# LED-DRIVER.net
KiCad netlist of a schematic drawn in Altium Designer
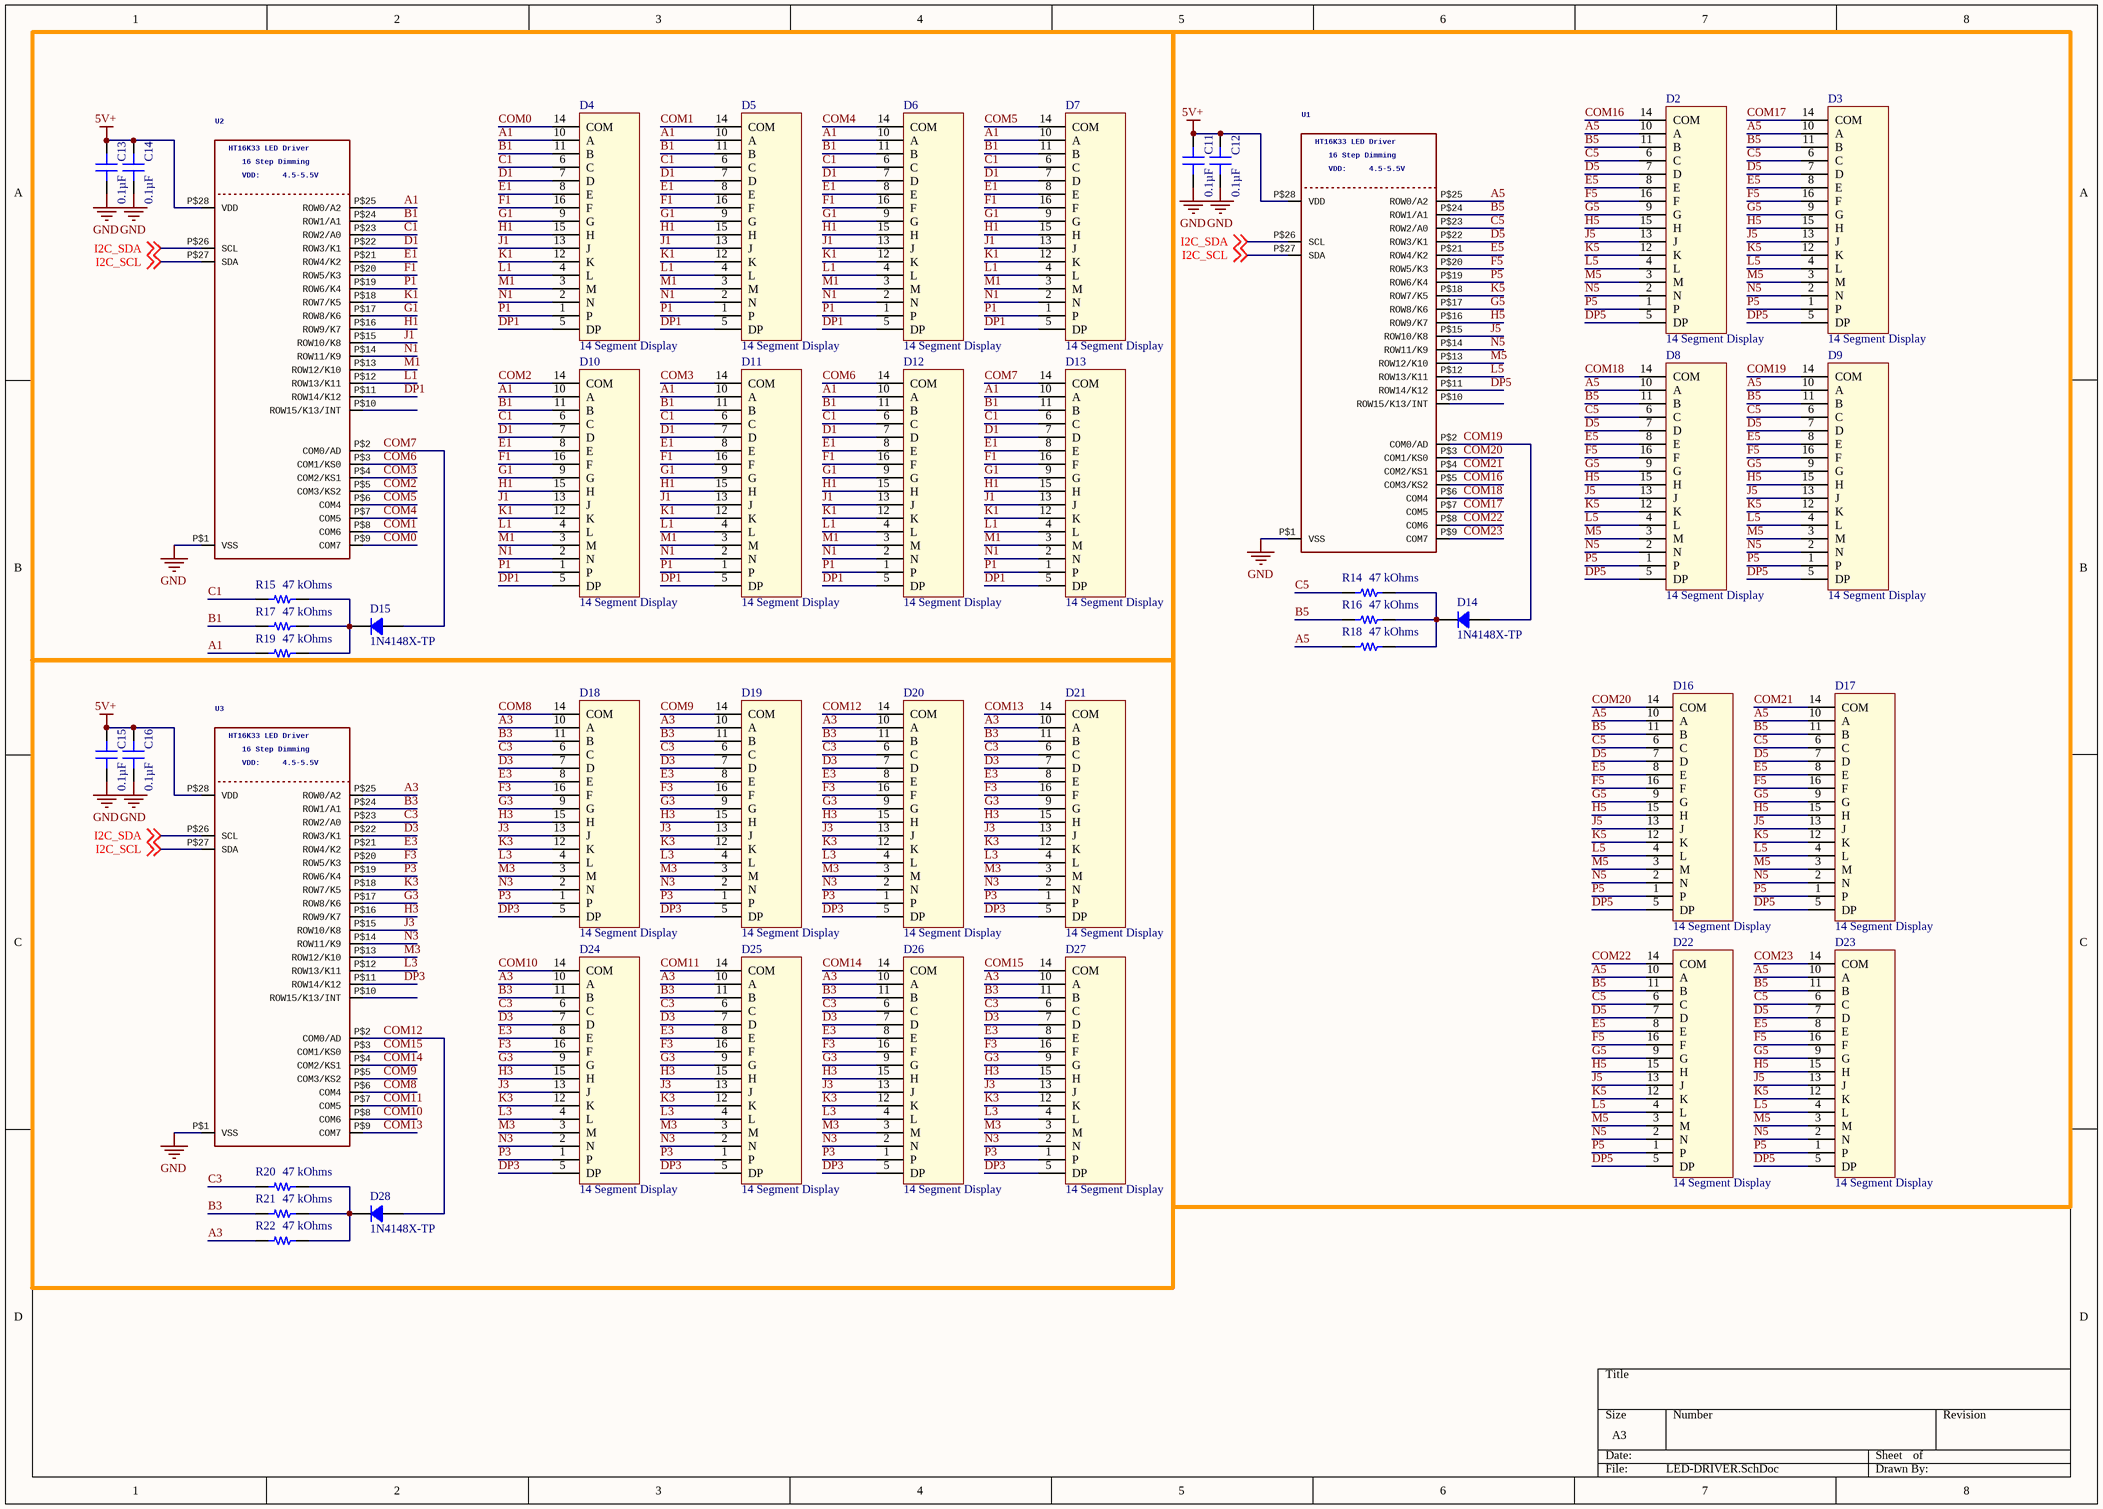
[diagram p0: LED-DRIVER.SchDoc]

(export (version "E")
  (design (tool "Eeschema 10.0.6"))
  (components
    (comp (ref "C11")
      (value "0.1µF")
      (footprint "CAP 0603_1608")
      (description "CAP CER 0.1UF 25V X7R 0603")
      (fields (field (name "PART NUMBER") "C0603T104K3RAL7867") (field (name "MANUFACTURER") "KEMET"))
      (libsource (lib "Altium Master") (part "Capacitor"))
    )
    (comp (ref "C12")
      (value "0.1µF")
      (footprint "CAP 0603_1608")
      (description "CAP CER 0.1UF 25V X7R 0603")
      (fields (field (name "PART NUMBER") "C0603T104K3RAL7867") (field (name "MANUFACTURER") "KEMET"))
      (libsource (lib "Altium Master") (part "Capacitor"))
    )
    (comp (ref "C13")
      (value "0.1µF")
      (footprint "CAP 0603_1608")
      (description "CAP CER 0.1UF 25V X7R 0603")
      (fields (field (name "PART NUMBER") "C0603T104K3RAL7867") (field (name "MANUFACTURER") "KEMET"))
      (libsource (lib "Altium Master") (part "Capacitor"))
    )
    (comp (ref "C14")
      (value "0.1µF")
      (footprint "CAP 0603_1608")
      (description "CAP CER 0.1UF 25V X7R 0603")
      (fields (field (name "PART NUMBER") "C0603T104K3RAL7867") (field (name "MANUFACTURER") "KEMET"))
      (libsource (lib "Altium Master") (part "Capacitor"))
    )
    (comp (ref "C15")
      (value "0.1µF")
      (footprint "CAP 0603_1608")
      (description "CAP CER 0.1UF 25V X7R 0603")
      (fields (field (name "PART NUMBER") "C0603T104K3RAL7867") (field (name "MANUFACTURER") "KEMET"))
      (libsource (lib "Altium Master") (part "Capacitor"))
    )
    (comp (ref "C16")
      (value "0.1µF")
      (footprint "CAP 0603_1608")
      (description "CAP CER 0.1UF 25V X7R 0603")
      (fields (field (name "PART NUMBER") "C0603T104K3RAL7867") (field (name "MANUFACTURER") "KEMET"))
      (libsource (lib "Altium Master") (part "Capacitor"))
    )
    (comp (ref "D2")
      (value "14 Segment Display")
      (footprint "14 Seg Display")
      (description "14 Segment display red 2 char")
      (libsource (lib "Lib") (part "14 Segment Display"))
    )
    (comp (ref "D3")
      (value "14 Segment Display")
      (footprint "14 Seg Display")
      (description "14 Segment display red 2 char")
      (libsource (lib "Lib") (part "14 Segment Display"))
    )
    (comp (ref "D4")
      (value "14 Segment Display")
      (footprint "14 Seg Display")
      (description "14 Segment display red 2 char")
      (libsource (lib "Lib") (part "14 Segment Display"))
    )
    (comp (ref "D5")
      (value "14 Segment Display")
      (footprint "14 Seg Display")
      (description "14 Segment display red 2 char")
      (libsource (lib "Lib") (part "14 Segment Display"))
    )
    (comp (ref "D6")
      (value "14 Segment Display")
      (footprint "14 Seg Display")
      (description "14 Segment display red 2 char")
      (libsource (lib "Lib") (part "14 Segment Display"))
    )
    (comp (ref "D7")
      (value "14 Segment Display")
      (footprint "14 Seg Display")
      (description "14 Segment display red 2 char")
      (libsource (lib "Lib") (part "14 Segment Display"))
    )
    (comp (ref "D8")
      (value "14 Segment Display")
      (footprint "14 Seg Display")
      (description "14 Segment display red 2 char")
      (libsource (lib "Lib") (part "14 Segment Display"))
    )
    (comp (ref "D9")
      (value "14 Segment Display")
      (footprint "14 Seg Display")
      (description "14 Segment display red 2 char")
      (libsource (lib "Lib") (part "14 Segment Display"))
    )
    (comp (ref "D10")
      (value "14 Segment Display")
      (footprint "14 Seg Display")
      (description "14 Segment display red 2 char")
      (libsource (lib "Lib") (part "14 Segment Display"))
    )
    (comp (ref "D11")
      (value "14 Segment Display")
      (footprint "14 Seg Display")
      (description "14 Segment display red 2 char")
      (libsource (lib "Lib") (part "14 Segment Display"))
    )
    (comp (ref "D12")
      (value "14 Segment Display")
      (footprint "14 Seg Display")
      (description "14 Segment display red 2 char")
      (libsource (lib "Lib") (part "14 Segment Display"))
    )
    (comp (ref "D13")
      (value "14 Segment Display")
      (footprint "14 Seg Display")
      (description "14 Segment display red 2 char")
      (libsource (lib "Lib") (part "14 Segment Display"))
    )
    (comp (ref "D14")
      (value "1N4148X-TP")
      (footprint "SOD-523")
      (description "DIODE GEN PURP 75V 150MA SOD523")
      (fields (field (name "MANUFACTURER") "Micro Commercial Co"))
      (libsource (lib "Altium Master") (part "Diode"))
    )
    (comp (ref "D15")
      (value "1N4148X-TP")
      (footprint "SOD-523")
      (description "DIODE GEN PURP 75V 150MA SOD523")
      (fields (field (name "MANUFACTURER") "Micro Commercial Co"))
      (libsource (lib "Altium Master") (part "Diode"))
    )
    (comp (ref "D16")
      (value "14 Segment Display")
      (footprint "14 Seg Display")
      (description "14 Segment display red 2 char")
      (libsource (lib "Lib") (part "14 Segment Display"))
    )
    (comp (ref "D17")
      (value "14 Segment Display")
      (footprint "14 Seg Display")
      (description "14 Segment display red 2 char")
      (libsource (lib "Lib") (part "14 Segment Display"))
    )
    (comp (ref "D18")
      (value "14 Segment Display")
      (footprint "14 Seg Display")
      (description "14 Segment display red 2 char")
      (libsource (lib "Lib") (part "14 Segment Display"))
    )
    (comp (ref "D19")
      (value "14 Segment Display")
      (footprint "14 Seg Display")
      (description "14 Segment display red 2 char")
      (libsource (lib "Lib") (part "14 Segment Display"))
    )
    (comp (ref "D20")
      (value "14 Segment Display")
      (footprint "14 Seg Display")
      (description "14 Segment display red 2 char")
      (libsource (lib "Lib") (part "14 Segment Display"))
    )
    (comp (ref "D21")
      (value "14 Segment Display")
      (footprint "14 Seg Display")
      (description "14 Segment display red 2 char")
      (libsource (lib "Lib") (part "14 Segment Display"))
    )
    (comp (ref "D22")
      (value "14 Segment Display")
      (footprint "14 Seg Display")
      (description "14 Segment display red 2 char")
      (libsource (lib "Lib") (part "14 Segment Display"))
    )
    (comp (ref "D23")
      (value "14 Segment Display")
      (footprint "14 Seg Display")
      (description "14 Segment display red 2 char")
      (libsource (lib "Lib") (part "14 Segment Display"))
    )
    (comp (ref "D24")
      (value "14 Segment Display")
      (footprint "14 Seg Display")
      (description "14 Segment display red 2 char")
      (libsource (lib "Lib") (part "14 Segment Display"))
    )
    (comp (ref "D25")
      (value "14 Segment Display")
      (footprint "14 Seg Display")
      (description "14 Segment display red 2 char")
      (libsource (lib "Lib") (part "14 Segment Display"))
    )
    (comp (ref "D26")
      (value "14 Segment Display")
      (footprint "14 Seg Display")
      (description "14 Segment display red 2 char")
      (libsource (lib "Lib") (part "14 Segment Display"))
    )
    (comp (ref "D27")
      (value "14 Segment Display")
      (footprint "14 Seg Display")
      (description "14 Segment display red 2 char")
      (libsource (lib "Lib") (part "14 Segment Display"))
    )
    (comp (ref "D28")
      (value "1N4148X-TP")
      (footprint "SOD-523")
      (description "DIODE GEN PURP 75V 150MA SOD523")
      (fields (field (name "MANUFACTURER") "Micro Commercial Co"))
      (libsource (lib "Altium Master") (part "Diode"))
    )
    (comp (ref "R14")
      (value "47 kOhms")
      (footprint "RES 0603_1608")
      (description "RES SMD 47K OHM 0.1% 1/10W 0603")
      (fields
        (field (name "PART NUMBER") "ERA-3AEB473V")
        (field (name "MANUFACTURER") "Panasonic Electronic Components")
      )
      (libsource (lib "Altium Master") (part "Resistor"))
    )
    (comp (ref "R15")
      (value "47 kOhms")
      (footprint "RES 0603_1608")
      (description "RES SMD 47K OHM 0.1% 1/10W 0603")
      (fields
        (field (name "PART NUMBER") "ERA-3AEB473V")
        (field (name "MANUFACTURER") "Panasonic Electronic Components")
      )
      (libsource (lib "Altium Master") (part "Resistor"))
    )
    (comp (ref "R16")
      (value "47 kOhms")
      (footprint "RES 0603_1608")
      (description "RES SMD 47K OHM 0.1% 1/10W 0603")
      (fields
        (field (name "PART NUMBER") "ERA-3AEB473V")
        (field (name "MANUFACTURER") "Panasonic Electronic Components")
      )
      (libsource (lib "Altium Master") (part "Resistor"))
    )
    (comp (ref "R17")
      (value "47 kOhms")
      (footprint "RES 0603_1608")
      (description "RES SMD 47K OHM 0.1% 1/10W 0603")
      (fields
        (field (name "PART NUMBER") "ERA-3AEB473V")
        (field (name "MANUFACTURER") "Panasonic Electronic Components")
      )
      (libsource (lib "Altium Master") (part "Resistor"))
    )
    (comp (ref "R18")
      (value "47 kOhms")
      (footprint "RES 0603_1608")
      (description "RES SMD 47K OHM 0.1% 1/10W 0603")
      (fields
        (field (name "PART NUMBER") "ERA-3AEB473V")
        (field (name "MANUFACTURER") "Panasonic Electronic Components")
      )
      (libsource (lib "Altium Master") (part "Resistor"))
    )
    (comp (ref "R19")
      (value "47 kOhms")
      (footprint "RES 0603_1608")
      (description "RES SMD 47K OHM 0.1% 1/10W 0603")
      (fields
        (field (name "PART NUMBER") "ERA-3AEB473V")
        (field (name "MANUFACTURER") "Panasonic Electronic Components")
      )
      (libsource (lib "Altium Master") (part "Resistor"))
    )
    (comp (ref "R20")
      (value "47 kOhms")
      (footprint "RES 0603_1608")
      (description "RES SMD 47K OHM 0.1% 1/10W 0603")
      (fields
        (field (name "PART NUMBER") "ERA-3AEB473V")
        (field (name "MANUFACTURER") "Panasonic Electronic Components")
      )
      (libsource (lib "Altium Master") (part "Resistor"))
    )
    (comp (ref "R21")
      (value "47 kOhms")
      (footprint "RES 0603_1608")
      (description "RES SMD 47K OHM 0.1% 1/10W 0603")
      (fields
        (field (name "PART NUMBER") "ERA-3AEB473V")
        (field (name "MANUFACTURER") "Panasonic Electronic Components")
      )
      (libsource (lib "Altium Master") (part "Resistor"))
    )
    (comp (ref "R22")
      (value "47 kOhms")
      (footprint "RES 0603_1608")
      (description "RES SMD 47K OHM 0.1% 1/10W 0603")
      (fields
        (field (name "PART NUMBER") "ERA-3AEB473V")
        (field (name "MANUFACTURER") "Panasonic Electronic Components")
      )
      (libsource (lib "Altium Master") (part "Resistor"))
    )
    (comp (ref "U1")
      (value "HT16K33_SOP28_SKINNY")
      (footprint "SOP28_300MIL_SKINNY")
      (fields
        (field (name "HT16K33LEDDRIVER") "HT16K33 LED Driver")
        (field (name "VDD") "VDD:")
        (field (name "4.5-5.5V") "4.5-5.5V")
        (field (name "16STEPDIMMING") "16 Step Dimming")
      )
      (libsource (lib "AlphaNumeric Featherwing rev A") (part "HT16K33_SOP28_SKINNY"))
    )
    (comp (ref "U2")
      (value "HT16K33_SOP28_SKINNY")
      (footprint "SOP28_300MIL_SKINNY")
      (fields
        (field (name "HT16K33LEDDRIVER") "HT16K33 LED Driver")
        (field (name "VDD") "VDD:")
        (field (name "4.5-5.5V") "4.5-5.5V")
        (field (name "16STEPDIMMING") "16 Step Dimming")
      )
      (libsource (lib "AlphaNumeric Featherwing rev A") (part "HT16K33_SOP28_SKINNY"))
    )
    (comp (ref "U3")
      (value "HT16K33_SOP28_SKINNY")
      (footprint "SOP28_300MIL_SKINNY")
      (fields
        (field (name "HT16K33LEDDRIVER") "HT16K33 LED Driver")
        (field (name "VDD") "VDD:")
        (field (name "4.5-5.5V") "4.5-5.5V")
        (field (name "16STEPDIMMING") "16 Step Dimming")
      )
      (libsource (lib "AlphaNumeric Featherwing rev A") (part "HT16K33_SOP28_SKINNY"))
    )
  )
  (nets
    (net (code "1") (name "/A1") (class "Default")
      (node (ref "D10") (pin "10") (pinfunction "A_10") (pintype "power_in"))
      (node (ref "D11") (pin "10") (pinfunction "A_10") (pintype "power_in"))
      (node (ref "D12") (pin "10") (pinfunction "A_10") (pintype "power_in"))
      (node (ref "D13") (pin "10") (pinfunction "A_10") (pintype "power_in"))
      (node (ref "D4") (pin "10") (pinfunction "A_10") (pintype "power_in"))
      (node (ref "D5") (pin "10") (pinfunction "A_10") (pintype "power_in"))
      (node (ref "D6") (pin "10") (pinfunction "A_10") (pintype "power_in"))
      (node (ref "D7") (pin "10") (pinfunction "A_10") (pintype "power_in"))
      (node (ref "R19") (pin "1") (pinfunction "1_1") (pintype "passive"))
      (node (ref "U2") (pin "P$25") (pinfunction "ROW0/A2_P$25") (pintype "bidirectional"))
    )
    (net (code "2") (name "/A3") (class "Default")
      (node (ref "D18") (pin "10") (pinfunction "A_10") (pintype "power_in"))
      (node (ref "D19") (pin "10") (pinfunction "A_10") (pintype "power_in"))
      (node (ref "D20") (pin "10") (pinfunction "A_10") (pintype "power_in"))
      (node (ref "D21") (pin "10") (pinfunction "A_10") (pintype "power_in"))
      (node (ref "D24") (pin "10") (pinfunction "A_10") (pintype "power_in"))
      (node (ref "D25") (pin "10") (pinfunction "A_10") (pintype "power_in"))
      (node (ref "D26") (pin "10") (pinfunction "A_10") (pintype "power_in"))
      (node (ref "D27") (pin "10") (pinfunction "A_10") (pintype "power_in"))
      (node (ref "R22") (pin "1") (pinfunction "1_1") (pintype "passive"))
      (node (ref "U3") (pin "P$25") (pinfunction "ROW0/A2_P$25") (pintype "bidirectional"))
    )
    (net (code "3") (name "/A5") (class "Default")
      (node (ref "D16") (pin "10") (pinfunction "A_10") (pintype "power_in"))
      (node (ref "D17") (pin "10") (pinfunction "A_10") (pintype "power_in"))
      (node (ref "D2") (pin "10") (pinfunction "A_10") (pintype "power_in"))
      (node (ref "D22") (pin "10") (pinfunction "A_10") (pintype "power_in"))
      (node (ref "D23") (pin "10") (pinfunction "A_10") (pintype "power_in"))
      (node (ref "D3") (pin "10") (pinfunction "A_10") (pintype "power_in"))
      (node (ref "D8") (pin "10") (pinfunction "A_10") (pintype "power_in"))
      (node (ref "D9") (pin "10") (pinfunction "A_10") (pintype "power_in"))
      (node (ref "R18") (pin "1") (pinfunction "1_1") (pintype "passive"))
      (node (ref "U1") (pin "P$25") (pinfunction "ROW0/A2_P$25") (pintype "bidirectional"))
    )
    (net (code "4") (name "/B1") (class "Default")
      (node (ref "D10") (pin "11") (pinfunction "B_11") (pintype "power_in"))
      (node (ref "D11") (pin "11") (pinfunction "B_11") (pintype "power_in"))
      (node (ref "D12") (pin "11") (pinfunction "B_11") (pintype "power_in"))
      (node (ref "D13") (pin "11") (pinfunction "B_11") (pintype "power_in"))
      (node (ref "D4") (pin "11") (pinfunction "B_11") (pintype "power_in"))
      (node (ref "D5") (pin "11") (pinfunction "B_11") (pintype "power_in"))
      (node (ref "D6") (pin "11") (pinfunction "B_11") (pintype "power_in"))
      (node (ref "D7") (pin "11") (pinfunction "B_11") (pintype "power_in"))
      (node (ref "R17") (pin "1") (pinfunction "1_1") (pintype "passive"))
      (node (ref "U2") (pin "P$24") (pinfunction "ROW1/A1_P$24") (pintype "bidirectional"))
    )
    (net (code "5") (name "/B3") (class "Default")
      (node (ref "D18") (pin "11") (pinfunction "B_11") (pintype "power_in"))
      (node (ref "D19") (pin "11") (pinfunction "B_11") (pintype "power_in"))
      (node (ref "D20") (pin "11") (pinfunction "B_11") (pintype "power_in"))
      (node (ref "D21") (pin "11") (pinfunction "B_11") (pintype "power_in"))
      (node (ref "D24") (pin "11") (pinfunction "B_11") (pintype "power_in"))
      (node (ref "D25") (pin "11") (pinfunction "B_11") (pintype "power_in"))
      (node (ref "D26") (pin "11") (pinfunction "B_11") (pintype "power_in"))
      (node (ref "D27") (pin "11") (pinfunction "B_11") (pintype "power_in"))
      (node (ref "R21") (pin "1") (pinfunction "1_1") (pintype "passive"))
      (node (ref "U3") (pin "P$24") (pinfunction "ROW1/A1_P$24") (pintype "bidirectional"))
    )
    (net (code "6") (name "/B5") (class "Default")
      (node (ref "D16") (pin "11") (pinfunction "B_11") (pintype "power_in"))
      (node (ref "D17") (pin "11") (pinfunction "B_11") (pintype "power_in"))
      (node (ref "D2") (pin "11") (pinfunction "B_11") (pintype "power_in"))
      (node (ref "D22") (pin "11") (pinfunction "B_11") (pintype "power_in"))
      (node (ref "D23") (pin "11") (pinfunction "B_11") (pintype "power_in"))
      (node (ref "D3") (pin "11") (pinfunction "B_11") (pintype "power_in"))
      (node (ref "D8") (pin "11") (pinfunction "B_11") (pintype "power_in"))
      (node (ref "D9") (pin "11") (pinfunction "B_11") (pintype "power_in"))
      (node (ref "R16") (pin "1") (pinfunction "1_1") (pintype "passive"))
      (node (ref "U1") (pin "P$24") (pinfunction "ROW1/A1_P$24") (pintype "bidirectional"))
    )
    (net (code "7") (name "/C1") (class "Default")
      (node (ref "D10") (pin "6") (pinfunction "C_6") (pintype "power_in"))
      (node (ref "D11") (pin "6") (pinfunction "C_6") (pintype "power_in"))
      (node (ref "D12") (pin "6") (pinfunction "C_6") (pintype "power_in"))
      (node (ref "D13") (pin "6") (pinfunction "C_6") (pintype "power_in"))
      (node (ref "D4") (pin "6") (pinfunction "C_6") (pintype "power_in"))
      (node (ref "D5") (pin "6") (pinfunction "C_6") (pintype "power_in"))
      (node (ref "D6") (pin "6") (pinfunction "C_6") (pintype "power_in"))
      (node (ref "D7") (pin "6") (pinfunction "C_6") (pintype "power_in"))
      (node (ref "R15") (pin "1") (pinfunction "1_1") (pintype "passive"))
      (node (ref "U2") (pin "P$23") (pinfunction "ROW2/A0_P$23") (pintype "bidirectional"))
    )
    (net (code "8") (name "/C3") (class "Default")
      (node (ref "D18") (pin "6") (pinfunction "C_6") (pintype "power_in"))
      (node (ref "D19") (pin "6") (pinfunction "C_6") (pintype "power_in"))
      (node (ref "D20") (pin "6") (pinfunction "C_6") (pintype "power_in"))
      (node (ref "D21") (pin "6") (pinfunction "C_6") (pintype "power_in"))
      (node (ref "D24") (pin "6") (pinfunction "C_6") (pintype "power_in"))
      (node (ref "D25") (pin "6") (pinfunction "C_6") (pintype "power_in"))
      (node (ref "D26") (pin "6") (pinfunction "C_6") (pintype "power_in"))
      (node (ref "D27") (pin "6") (pinfunction "C_6") (pintype "power_in"))
      (node (ref "R20") (pin "1") (pinfunction "1_1") (pintype "passive"))
      (node (ref "U3") (pin "P$23") (pinfunction "ROW2/A0_P$23") (pintype "bidirectional"))
    )
    (net (code "9") (name "/C5") (class "Default")
      (node (ref "D16") (pin "6") (pinfunction "C_6") (pintype "power_in"))
      (node (ref "D17") (pin "6") (pinfunction "C_6") (pintype "power_in"))
      (node (ref "D2") (pin "6") (pinfunction "C_6") (pintype "power_in"))
      (node (ref "D22") (pin "6") (pinfunction "C_6") (pintype "power_in"))
      (node (ref "D23") (pin "6") (pinfunction "C_6") (pintype "power_in"))
      (node (ref "D3") (pin "6") (pinfunction "C_6") (pintype "power_in"))
      (node (ref "D8") (pin "6") (pinfunction "C_6") (pintype "power_in"))
      (node (ref "D9") (pin "6") (pinfunction "C_6") (pintype "power_in"))
      (node (ref "R14") (pin "1") (pinfunction "1_1") (pintype "passive"))
      (node (ref "U1") (pin "P$23") (pinfunction "ROW2/A0_P$23") (pintype "bidirectional"))
    )
    (net (code "10") (name "/COM0") (class "Default")
      (node (ref "D4") (pin "14") (pinfunction "COM_14") (pintype "power_in"))
      (node (ref "U2") (pin "P$9") (pinfunction "COM7_P$9") (pintype "bidirectional"))
    )
    (net (code "11") (name "/COM1") (class "Default")
      (node (ref "D5") (pin "14") (pinfunction "COM_14") (pintype "power_in"))
      (node (ref "U2") (pin "P$8") (pinfunction "COM6_P$8") (pintype "bidirectional"))
    )
    (net (code "12") (name "/COM2") (class "Default")
      (node (ref "D10") (pin "14") (pinfunction "COM_14") (pintype "power_in"))
      (node (ref "U2") (pin "P$5") (pinfunction "COM3/KS2_P$5") (pintype "bidirectional"))
    )
    (net (code "13") (name "/COM3") (class "Default")
      (node (ref "D11") (pin "14") (pinfunction "COM_14") (pintype "power_in"))
      (node (ref "U2") (pin "P$4") (pinfunction "COM2/KS1_P$4") (pintype "bidirectional"))
    )
    (net (code "14") (name "/COM4") (class "Default")
      (node (ref "D6") (pin "14") (pinfunction "COM_14") (pintype "power_in"))
      (node (ref "U2") (pin "P$7") (pinfunction "COM5_P$7") (pintype "bidirectional"))
    )
    (net (code "15") (name "/COM5") (class "Default")
      (node (ref "D7") (pin "14") (pinfunction "COM_14") (pintype "power_in"))
      (node (ref "U2") (pin "P$6") (pinfunction "COM4_P$6") (pintype "bidirectional"))
    )
    (net (code "16") (name "/COM6") (class "Default")
      (node (ref "D12") (pin "14") (pinfunction "COM_14") (pintype "power_in"))
      (node (ref "U2") (pin "P$3") (pinfunction "COM1/KS0_P$3") (pintype "bidirectional"))
    )
    (net (code "17") (name "/COM7") (class "Default")
      (node (ref "D13") (pin "14") (pinfunction "COM_14") (pintype "power_in"))
      (node (ref "D15") (pin "1") (pinfunction "1_1") (pintype "passive"))
      (node (ref "U2") (pin "P$2") (pinfunction "COM0/AD_P$2") (pintype "bidirectional"))
    )
    (net (code "18") (name "/COM8") (class "Default")
      (node (ref "D18") (pin "14") (pinfunction "COM_14") (pintype "power_in"))
      (node (ref "U3") (pin "P$6") (pinfunction "COM4_P$6") (pintype "bidirectional"))
    )
    (net (code "19") (name "/COM9") (class "Default")
      (node (ref "D19") (pin "14") (pinfunction "COM_14") (pintype "power_in"))
      (node (ref "U3") (pin "P$5") (pinfunction "COM3/KS2_P$5") (pintype "bidirectional"))
    )
    (net (code "20") (name "/COM10") (class "Default")
      (node (ref "D24") (pin "14") (pinfunction "COM_14") (pintype "power_in"))
      (node (ref "U3") (pin "P$8") (pinfunction "COM6_P$8") (pintype "bidirectional"))
    )
    (net (code "21") (name "/COM11") (class "Default")
      (node (ref "D25") (pin "14") (pinfunction "COM_14") (pintype "power_in"))
      (node (ref "U3") (pin "P$7") (pinfunction "COM5_P$7") (pintype "bidirectional"))
    )
    (net (code "22") (name "/COM12") (class "Default")
      (node (ref "D20") (pin "14") (pinfunction "COM_14") (pintype "power_in"))
      (node (ref "D28") (pin "1") (pinfunction "1_1") (pintype "passive"))
      (node (ref "U3") (pin "P$2") (pinfunction "COM0/AD_P$2") (pintype "bidirectional"))
    )
    (net (code "23") (name "/COM13") (class "Default")
      (node (ref "D21") (pin "14") (pinfunction "COM_14") (pintype "power_in"))
      (node (ref "U3") (pin "P$9") (pinfunction "COM7_P$9") (pintype "bidirectional"))
    )
    (net (code "24") (name "/COM14") (class "Default")
      (node (ref "D26") (pin "14") (pinfunction "COM_14") (pintype "power_in"))
      (node (ref "U3") (pin "P$4") (pinfunction "COM2/KS1_P$4") (pintype "bidirectional"))
    )
    (net (code "25") (name "/COM15") (class "Default")
      (node (ref "D27") (pin "14") (pinfunction "COM_14") (pintype "power_in"))
      (node (ref "U3") (pin "P$3") (pinfunction "COM1/KS0_P$3") (pintype "bidirectional"))
    )
    (net (code "26") (name "/COM16") (class "Default")
      (node (ref "D2") (pin "14") (pinfunction "COM_14") (pintype "power_in"))
      (node (ref "U1") (pin "P$5") (pinfunction "COM3/KS2_P$5") (pintype "bidirectional"))
    )
    (net (code "27") (name "/COM17") (class "Default")
      (node (ref "D3") (pin "14") (pinfunction "COM_14") (pintype "power_in"))
      (node (ref "U1") (pin "P$7") (pinfunction "COM5_P$7") (pintype "bidirectional"))
    )
    (net (code "28") (name "/COM18") (class "Default")
      (node (ref "D8") (pin "14") (pinfunction "COM_14") (pintype "power_in"))
      (node (ref "U1") (pin "P$6") (pinfunction "COM4_P$6") (pintype "bidirectional"))
    )
    (net (code "29") (name "/COM19") (class "Default")
      (node (ref "D14") (pin "1") (pinfunction "1_1") (pintype "passive"))
      (node (ref "D9") (pin "14") (pinfunction "COM_14") (pintype "power_in"))
      (node (ref "U1") (pin "P$2") (pinfunction "COM0/AD_P$2") (pintype "bidirectional"))
    )
    (net (code "30") (name "/COM20") (class "Default")
      (node (ref "D16") (pin "14") (pinfunction "COM_14") (pintype "power_in"))
      (node (ref "U1") (pin "P$3") (pinfunction "COM1/KS0_P$3") (pintype "bidirectional"))
    )
    (net (code "31") (name "/COM21") (class "Default")
      (node (ref "D17") (pin "14") (pinfunction "COM_14") (pintype "power_in"))
      (node (ref "U1") (pin "P$4") (pinfunction "COM2/KS1_P$4") (pintype "bidirectional"))
    )
    (net (code "32") (name "/COM22") (class "Default")
      (node (ref "D22") (pin "14") (pinfunction "COM_14") (pintype "power_in"))
      (node (ref "U1") (pin "P$8") (pinfunction "COM6_P$8") (pintype "bidirectional"))
    )
    (net (code "33") (name "/COM23") (class "Default")
      (node (ref "D23") (pin "14") (pinfunction "COM_14") (pintype "power_in"))
      (node (ref "U1") (pin "P$9") (pinfunction "COM7_P$9") (pintype "bidirectional"))
    )
    (net (code "34") (name "/D1") (class "Default")
      (node (ref "D10") (pin "7") (pinfunction "D_7") (pintype "power_in"))
      (node (ref "D11") (pin "7") (pinfunction "D_7") (pintype "power_in"))
      (node (ref "D12") (pin "7") (pinfunction "D_7") (pintype "power_in"))
      (node (ref "D13") (pin "7") (pinfunction "D_7") (pintype "power_in"))
      (node (ref "D4") (pin "7") (pinfunction "D_7") (pintype "power_in"))
      (node (ref "D5") (pin "7") (pinfunction "D_7") (pintype "power_in"))
      (node (ref "D6") (pin "7") (pinfunction "D_7") (pintype "power_in"))
      (node (ref "D7") (pin "7") (pinfunction "D_7") (pintype "power_in"))
      (node (ref "U2") (pin "P$22") (pinfunction "ROW3/K1_P$22") (pintype "bidirectional"))
    )
    (net (code "35") (name "/D3") (class "Default")
      (node (ref "D18") (pin "7") (pinfunction "D_7") (pintype "power_in"))
      (node (ref "D19") (pin "7") (pinfunction "D_7") (pintype "power_in"))
      (node (ref "D20") (pin "7") (pinfunction "D_7") (pintype "power_in"))
      (node (ref "D21") (pin "7") (pinfunction "D_7") (pintype "power_in"))
      (node (ref "D24") (pin "7") (pinfunction "D_7") (pintype "power_in"))
      (node (ref "D25") (pin "7") (pinfunction "D_7") (pintype "power_in"))
      (node (ref "D26") (pin "7") (pinfunction "D_7") (pintype "power_in"))
      (node (ref "D27") (pin "7") (pinfunction "D_7") (pintype "power_in"))
      (node (ref "U3") (pin "P$22") (pinfunction "ROW3/K1_P$22") (pintype "bidirectional"))
    )
    (net (code "36") (name "/D5") (class "Default")
      (node (ref "D16") (pin "7") (pinfunction "D_7") (pintype "power_in"))
      (node (ref "D17") (pin "7") (pinfunction "D_7") (pintype "power_in"))
      (node (ref "D2") (pin "7") (pinfunction "D_7") (pintype "power_in"))
      (node (ref "D22") (pin "7") (pinfunction "D_7") (pintype "power_in"))
      (node (ref "D23") (pin "7") (pinfunction "D_7") (pintype "power_in"))
      (node (ref "D3") (pin "7") (pinfunction "D_7") (pintype "power_in"))
      (node (ref "D8") (pin "7") (pinfunction "D_7") (pintype "power_in"))
      (node (ref "D9") (pin "7") (pinfunction "D_7") (pintype "power_in"))
      (node (ref "U1") (pin "P$22") (pinfunction "ROW3/K1_P$22") (pintype "bidirectional"))
    )
    (net (code "37") (name "/DP1") (class "Default")
      (node (ref "D10") (pin "5") (pinfunction "DP_5") (pintype "power_in"))
      (node (ref "D11") (pin "5") (pinfunction "DP_5") (pintype "power_in"))
      (node (ref "D12") (pin "5") (pinfunction "DP_5") (pintype "power_in"))
      (node (ref "D13") (pin "5") (pinfunction "DP_5") (pintype "power_in"))
      (node (ref "D4") (pin "5") (pinfunction "DP_5") (pintype "power_in"))
      (node (ref "D5") (pin "5") (pinfunction "DP_5") (pintype "power_in"))
      (node (ref "D6") (pin "5") (pinfunction "DP_5") (pintype "power_in"))
      (node (ref "D7") (pin "5") (pinfunction "DP_5") (pintype "power_in"))
      (node (ref "U2") (pin "P$11") (pinfunction "ROW14/K12_P$11") (pintype "bidirectional"))
    )
    (net (code "38") (name "/DP3") (class "Default")
      (node (ref "D18") (pin "5") (pinfunction "DP_5") (pintype "power_in"))
      (node (ref "D19") (pin "5") (pinfunction "DP_5") (pintype "power_in"))
      (node (ref "D20") (pin "5") (pinfunction "DP_5") (pintype "power_in"))
      (node (ref "D21") (pin "5") (pinfunction "DP_5") (pintype "power_in"))
      (node (ref "D24") (pin "5") (pinfunction "DP_5") (pintype "power_in"))
      (node (ref "D25") (pin "5") (pinfunction "DP_5") (pintype "power_in"))
      (node (ref "D26") (pin "5") (pinfunction "DP_5") (pintype "power_in"))
      (node (ref "D27") (pin "5") (pinfunction "DP_5") (pintype "power_in"))
      (node (ref "U3") (pin "P$11") (pinfunction "ROW14/K12_P$11") (pintype "bidirectional"))
    )
    (net (code "39") (name "/DP5") (class "Default")
      (node (ref "D16") (pin "5") (pinfunction "DP_5") (pintype "power_in"))
      (node (ref "D17") (pin "5") (pinfunction "DP_5") (pintype "power_in"))
      (node (ref "D2") (pin "5") (pinfunction "DP_5") (pintype "power_in"))
      (node (ref "D22") (pin "5") (pinfunction "DP_5") (pintype "power_in"))
      (node (ref "D23") (pin "5") (pinfunction "DP_5") (pintype "power_in"))
      (node (ref "D3") (pin "5") (pinfunction "DP_5") (pintype "power_in"))
      (node (ref "D8") (pin "5") (pinfunction "DP_5") (pintype "power_in"))
      (node (ref "D9") (pin "5") (pinfunction "DP_5") (pintype "power_in"))
      (node (ref "U1") (pin "P$11") (pinfunction "ROW14/K12_P$11") (pintype "bidirectional"))
    )
    (net (code "40") (name "/E1") (class "Default")
      (node (ref "D10") (pin "8") (pinfunction "E_8") (pintype "power_in"))
      (node (ref "D11") (pin "8") (pinfunction "E_8") (pintype "power_in"))
      (node (ref "D12") (pin "8") (pinfunction "E_8") (pintype "power_in"))
      (node (ref "D13") (pin "8") (pinfunction "E_8") (pintype "power_in"))
      (node (ref "D4") (pin "8") (pinfunction "E_8") (pintype "power_in"))
      (node (ref "D5") (pin "8") (pinfunction "E_8") (pintype "power_in"))
      (node (ref "D6") (pin "8") (pinfunction "E_8") (pintype "power_in"))
      (node (ref "D7") (pin "8") (pinfunction "E_8") (pintype "power_in"))
      (node (ref "U2") (pin "P$21") (pinfunction "ROW4/K2_P$21") (pintype "bidirectional"))
    )
    (net (code "41") (name "/E3") (class "Default")
      (node (ref "D18") (pin "8") (pinfunction "E_8") (pintype "power_in"))
      (node (ref "D19") (pin "8") (pinfunction "E_8") (pintype "power_in"))
      (node (ref "D20") (pin "8") (pinfunction "E_8") (pintype "power_in"))
      (node (ref "D21") (pin "8") (pinfunction "E_8") (pintype "power_in"))
      (node (ref "D24") (pin "8") (pinfunction "E_8") (pintype "power_in"))
      (node (ref "D25") (pin "8") (pinfunction "E_8") (pintype "power_in"))
      (node (ref "D26") (pin "8") (pinfunction "E_8") (pintype "power_in"))
      (node (ref "D27") (pin "8") (pinfunction "E_8") (pintype "power_in"))
      (node (ref "U3") (pin "P$21") (pinfunction "ROW4/K2_P$21") (pintype "bidirectional"))
    )
    (net (code "42") (name "/E5") (class "Default")
      (node (ref "D16") (pin "8") (pinfunction "E_8") (pintype "power_in"))
      (node (ref "D17") (pin "8") (pinfunction "E_8") (pintype "power_in"))
      (node (ref "D2") (pin "8") (pinfunction "E_8") (pintype "power_in"))
      (node (ref "D22") (pin "8") (pinfunction "E_8") (pintype "power_in"))
      (node (ref "D23") (pin "8") (pinfunction "E_8") (pintype "power_in"))
      (node (ref "D3") (pin "8") (pinfunction "E_8") (pintype "power_in"))
      (node (ref "D8") (pin "8") (pinfunction "E_8") (pintype "power_in"))
      (node (ref "D9") (pin "8") (pinfunction "E_8") (pintype "power_in"))
      (node (ref "U1") (pin "P$21") (pinfunction "ROW4/K2_P$21") (pintype "bidirectional"))
    )
    (net (code "43") (name "/F1") (class "Default")
      (node (ref "D10") (pin "16") (pinfunction "F_16") (pintype "power_in"))
      (node (ref "D11") (pin "16") (pinfunction "F_16") (pintype "power_in"))
      (node (ref "D12") (pin "16") (pinfunction "F_16") (pintype "power_in"))
      (node (ref "D13") (pin "16") (pinfunction "F_16") (pintype "power_in"))
      (node (ref "D4") (pin "16") (pinfunction "F_16") (pintype "power_in"))
      (node (ref "D5") (pin "16") (pinfunction "F_16") (pintype "power_in"))
      (node (ref "D6") (pin "16") (pinfunction "F_16") (pintype "power_in"))
      (node (ref "D7") (pin "16") (pinfunction "F_16") (pintype "power_in"))
      (node (ref "U2") (pin "P$20") (pinfunction "ROW5/K3_P$20") (pintype "bidirectional"))
    )
    (net (code "44") (name "/F3") (class "Default")
      (node (ref "D18") (pin "16") (pinfunction "F_16") (pintype "power_in"))
      (node (ref "D19") (pin "16") (pinfunction "F_16") (pintype "power_in"))
      (node (ref "D20") (pin "16") (pinfunction "F_16") (pintype "power_in"))
      (node (ref "D21") (pin "16") (pinfunction "F_16") (pintype "power_in"))
      (node (ref "D24") (pin "16") (pinfunction "F_16") (pintype "power_in"))
      (node (ref "D25") (pin "16") (pinfunction "F_16") (pintype "power_in"))
      (node (ref "D26") (pin "16") (pinfunction "F_16") (pintype "power_in"))
      (node (ref "D27") (pin "16") (pinfunction "F_16") (pintype "power_in"))
      (node (ref "U3") (pin "P$20") (pinfunction "ROW5/K3_P$20") (pintype "bidirectional"))
    )
    (net (code "45") (name "/F5") (class "Default")
      (node (ref "D16") (pin "16") (pinfunction "F_16") (pintype "power_in"))
      (node (ref "D17") (pin "16") (pinfunction "F_16") (pintype "power_in"))
      (node (ref "D2") (pin "16") (pinfunction "F_16") (pintype "power_in"))
      (node (ref "D22") (pin "16") (pinfunction "F_16") (pintype "power_in"))
      (node (ref "D23") (pin "16") (pinfunction "F_16") (pintype "power_in"))
      (node (ref "D3") (pin "16") (pinfunction "F_16") (pintype "power_in"))
      (node (ref "D8") (pin "16") (pinfunction "F_16") (pintype "power_in"))
      (node (ref "D9") (pin "16") (pinfunction "F_16") (pintype "power_in"))
      (node (ref "U1") (pin "P$20") (pinfunction "ROW5/K3_P$20") (pintype "bidirectional"))
    )
    (net (code "46") (name "/G1") (class "Default")
      (node (ref "D10") (pin "9") (pinfunction "G_9") (pintype "power_in"))
      (node (ref "D11") (pin "9") (pinfunction "G_9") (pintype "power_in"))
      (node (ref "D12") (pin "9") (pinfunction "G_9") (pintype "power_in"))
      (node (ref "D13") (pin "9") (pinfunction "G_9") (pintype "power_in"))
      (node (ref "D4") (pin "9") (pinfunction "G_9") (pintype "power_in"))
      (node (ref "D5") (pin "9") (pinfunction "G_9") (pintype "power_in"))
      (node (ref "D6") (pin "9") (pinfunction "G_9") (pintype "power_in"))
      (node (ref "D7") (pin "9") (pinfunction "G_9") (pintype "power_in"))
      (node (ref "U2") (pin "P$17") (pinfunction "ROW8/K6_P$17") (pintype "bidirectional"))
    )
    (net (code "47") (name "/G3") (class "Default")
      (node (ref "D18") (pin "9") (pinfunction "G_9") (pintype "power_in"))
      (node (ref "D19") (pin "9") (pinfunction "G_9") (pintype "power_in"))
      (node (ref "D20") (pin "9") (pinfunction "G_9") (pintype "power_in"))
      (node (ref "D21") (pin "9") (pinfunction "G_9") (pintype "power_in"))
      (node (ref "D24") (pin "9") (pinfunction "G_9") (pintype "power_in"))
      (node (ref "D25") (pin "9") (pinfunction "G_9") (pintype "power_in"))
      (node (ref "D26") (pin "9") (pinfunction "G_9") (pintype "power_in"))
      (node (ref "D27") (pin "9") (pinfunction "G_9") (pintype "power_in"))
      (node (ref "U3") (pin "P$17") (pinfunction "ROW8/K6_P$17") (pintype "bidirectional"))
    )
    (net (code "48") (name "/G5") (class "Default")
      (node (ref "D16") (pin "9") (pinfunction "G_9") (pintype "power_in"))
      (node (ref "D17") (pin "9") (pinfunction "G_9") (pintype "power_in"))
      (node (ref "D2") (pin "9") (pinfunction "G_9") (pintype "power_in"))
      (node (ref "D22") (pin "9") (pinfunction "G_9") (pintype "power_in"))
      (node (ref "D23") (pin "9") (pinfunction "G_9") (pintype "power_in"))
      (node (ref "D3") (pin "9") (pinfunction "G_9") (pintype "power_in"))
      (node (ref "D8") (pin "9") (pinfunction "G_9") (pintype "power_in"))
      (node (ref "D9") (pin "9") (pinfunction "G_9") (pintype "power_in"))
      (node (ref "U1") (pin "P$17") (pinfunction "ROW8/K6_P$17") (pintype "bidirectional"))
    )
    (net (code "49") (name "/H1") (class "Default")
      (node (ref "D10") (pin "15") (pinfunction "H_15") (pintype "power_in"))
      (node (ref "D11") (pin "15") (pinfunction "H_15") (pintype "power_in"))
      (node (ref "D12") (pin "15") (pinfunction "H_15") (pintype "power_in"))
      (node (ref "D13") (pin "15") (pinfunction "H_15") (pintype "power_in"))
      (node (ref "D4") (pin "15") (pinfunction "H_15") (pintype "power_in"))
      (node (ref "D5") (pin "15") (pinfunction "H_15") (pintype "power_in"))
      (node (ref "D6") (pin "15") (pinfunction "H_15") (pintype "power_in"))
      (node (ref "D7") (pin "15") (pinfunction "H_15") (pintype "power_in"))
      (node (ref "U2") (pin "P$16") (pinfunction "ROW9/K7_P$16") (pintype "bidirectional"))
    )
    (net (code "50") (name "/H3") (class "Default")
      (node (ref "D18") (pin "15") (pinfunction "H_15") (pintype "power_in"))
      (node (ref "D19") (pin "15") (pinfunction "H_15") (pintype "power_in"))
      (node (ref "D20") (pin "15") (pinfunction "H_15") (pintype "power_in"))
      (node (ref "D21") (pin "15") (pinfunction "H_15") (pintype "power_in"))
      (node (ref "D24") (pin "15") (pinfunction "H_15") (pintype "power_in"))
      (node (ref "D25") (pin "15") (pinfunction "H_15") (pintype "power_in"))
      (node (ref "D26") (pin "15") (pinfunction "H_15") (pintype "power_in"))
      (node (ref "D27") (pin "15") (pinfunction "H_15") (pintype "power_in"))
      (node (ref "U3") (pin "P$16") (pinfunction "ROW9/K7_P$16") (pintype "bidirectional"))
    )
    (net (code "51") (name "/H5") (class "Default")
      (node (ref "D16") (pin "15") (pinfunction "H_15") (pintype "power_in"))
      (node (ref "D17") (pin "15") (pinfunction "H_15") (pintype "power_in"))
      (node (ref "D2") (pin "15") (pinfunction "H_15") (pintype "power_in"))
      (node (ref "D22") (pin "15") (pinfunction "H_15") (pintype "power_in"))
      (node (ref "D23") (pin "15") (pinfunction "H_15") (pintype "power_in"))
      (node (ref "D3") (pin "15") (pinfunction "H_15") (pintype "power_in"))
      (node (ref "D8") (pin "15") (pinfunction "H_15") (pintype "power_in"))
      (node (ref "D9") (pin "15") (pinfunction "H_15") (pintype "power_in"))
      (node (ref "U1") (pin "P$16") (pinfunction "ROW9/K7_P$16") (pintype "bidirectional"))
    )
    (net (code "52") (name "/J1") (class "Default")
      (node (ref "D10") (pin "13") (pinfunction "J_13") (pintype "power_in"))
      (node (ref "D11") (pin "13") (pinfunction "J_13") (pintype "power_in"))
      (node (ref "D12") (pin "13") (pinfunction "J_13") (pintype "power_in"))
      (node (ref "D13") (pin "13") (pinfunction "J_13") (pintype "power_in"))
      (node (ref "D4") (pin "13") (pinfunction "J_13") (pintype "power_in"))
      (node (ref "D5") (pin "13") (pinfunction "J_13") (pintype "power_in"))
      (node (ref "D6") (pin "13") (pinfunction "J_13") (pintype "power_in"))
      (node (ref "D7") (pin "13") (pinfunction "J_13") (pintype "power_in"))
      (node (ref "U2") (pin "P$15") (pinfunction "ROW10/K8_P$15") (pintype "bidirectional"))
    )
    (net (code "53") (name "/J3") (class "Default")
      (node (ref "D18") (pin "13") (pinfunction "J_13") (pintype "power_in"))
      (node (ref "D19") (pin "13") (pinfunction "J_13") (pintype "power_in"))
      (node (ref "D20") (pin "13") (pinfunction "J_13") (pintype "power_in"))
      (node (ref "D21") (pin "13") (pinfunction "J_13") (pintype "power_in"))
      (node (ref "D24") (pin "13") (pinfunction "J_13") (pintype "power_in"))
      (node (ref "D25") (pin "13") (pinfunction "J_13") (pintype "power_in"))
      (node (ref "D26") (pin "13") (pinfunction "J_13") (pintype "power_in"))
      (node (ref "D27") (pin "13") (pinfunction "J_13") (pintype "power_in"))
      (node (ref "U3") (pin "P$15") (pinfunction "ROW10/K8_P$15") (pintype "bidirectional"))
    )
    (net (code "54") (name "/J5") (class "Default")
      (node (ref "D16") (pin "13") (pinfunction "J_13") (pintype "power_in"))
      (node (ref "D17") (pin "13") (pinfunction "J_13") (pintype "power_in"))
      (node (ref "D2") (pin "13") (pinfunction "J_13") (pintype "power_in"))
      (node (ref "D22") (pin "13") (pinfunction "J_13") (pintype "power_in"))
      (node (ref "D23") (pin "13") (pinfunction "J_13") (pintype "power_in"))
      (node (ref "D3") (pin "13") (pinfunction "J_13") (pintype "power_in"))
      (node (ref "D8") (pin "13") (pinfunction "J_13") (pintype "power_in"))
      (node (ref "D9") (pin "13") (pinfunction "J_13") (pintype "power_in"))
      (node (ref "U1") (pin "P$15") (pinfunction "ROW10/K8_P$15") (pintype "bidirectional"))
    )
    (net (code "55") (name "/K1") (class "Default")
      (node (ref "D10") (pin "12") (pinfunction "K_12") (pintype "power_in"))
      (node (ref "D11") (pin "12") (pinfunction "K_12") (pintype "power_in"))
      (node (ref "D12") (pin "12") (pinfunction "K_12") (pintype "power_in"))
      (node (ref "D13") (pin "12") (pinfunction "K_12") (pintype "power_in"))
      (node (ref "D4") (pin "12") (pinfunction "K_12") (pintype "power_in"))
      (node (ref "D5") (pin "12") (pinfunction "K_12") (pintype "power_in"))
      (node (ref "D6") (pin "12") (pinfunction "K_12") (pintype "power_in"))
      (node (ref "D7") (pin "12") (pinfunction "K_12") (pintype "power_in"))
      (node (ref "U2") (pin "P$18") (pinfunction "ROW7/K5_P$18") (pintype "bidirectional"))
    )
    (net (code "56") (name "/K3") (class "Default")
      (node (ref "D18") (pin "12") (pinfunction "K_12") (pintype "power_in"))
      (node (ref "D19") (pin "12") (pinfunction "K_12") (pintype "power_in"))
      (node (ref "D20") (pin "12") (pinfunction "K_12") (pintype "power_in"))
      (node (ref "D21") (pin "12") (pinfunction "K_12") (pintype "power_in"))
      (node (ref "D24") (pin "12") (pinfunction "K_12") (pintype "power_in"))
      (node (ref "D25") (pin "12") (pinfunction "K_12") (pintype "power_in"))
      (node (ref "D26") (pin "12") (pinfunction "K_12") (pintype "power_in"))
      (node (ref "D27") (pin "12") (pinfunction "K_12") (pintype "power_in"))
      (node (ref "U3") (pin "P$18") (pinfunction "ROW7/K5_P$18") (pintype "bidirectional"))
    )
    (net (code "57") (name "/K5") (class "Default")
      (node (ref "D16") (pin "12") (pinfunction "K_12") (pintype "power_in"))
      (node (ref "D17") (pin "12") (pinfunction "K_12") (pintype "power_in"))
      (node (ref "D2") (pin "12") (pinfunction "K_12") (pintype "power_in"))
      (node (ref "D22") (pin "12") (pinfunction "K_12") (pintype "power_in"))
      (node (ref "D23") (pin "12") (pinfunction "K_12") (pintype "power_in"))
      (node (ref "D3") (pin "12") (pinfunction "K_12") (pintype "power_in"))
      (node (ref "D8") (pin "12") (pinfunction "K_12") (pintype "power_in"))
      (node (ref "D9") (pin "12") (pinfunction "K_12") (pintype "power_in"))
      (node (ref "U1") (pin "P$18") (pinfunction "ROW7/K5_P$18") (pintype "bidirectional"))
    )
    (net (code "58") (name "/L1") (class "Default")
      (node (ref "D10") (pin "4") (pinfunction "L_4") (pintype "power_in"))
      (node (ref "D11") (pin "4") (pinfunction "L_4") (pintype "power_in"))
      (node (ref "D12") (pin "4") (pinfunction "L_4") (pintype "power_in"))
      (node (ref "D13") (pin "4") (pinfunction "L_4") (pintype "power_in"))
      (node (ref "D4") (pin "4") (pinfunction "L_4") (pintype "power_in"))
      (node (ref "D5") (pin "4") (pinfunction "L_4") (pintype "power_in"))
      (node (ref "D6") (pin "4") (pinfunction "L_4") (pintype "power_in"))
      (node (ref "D7") (pin "4") (pinfunction "L_4") (pintype "power_in"))
      (node (ref "U2") (pin "P$12") (pinfunction "ROW13/K11_P$12") (pintype "bidirectional"))
    )
    (net (code "59") (name "/L3") (class "Default")
      (node (ref "D18") (pin "4") (pinfunction "L_4") (pintype "power_in"))
      (node (ref "D19") (pin "4") (pinfunction "L_4") (pintype "power_in"))
      (node (ref "D20") (pin "4") (pinfunction "L_4") (pintype "power_in"))
      (node (ref "D21") (pin "4") (pinfunction "L_4") (pintype "power_in"))
      (node (ref "D24") (pin "4") (pinfunction "L_4") (pintype "power_in"))
      (node (ref "D25") (pin "4") (pinfunction "L_4") (pintype "power_in"))
      (node (ref "D26") (pin "4") (pinfunction "L_4") (pintype "power_in"))
      (node (ref "D27") (pin "4") (pinfunction "L_4") (pintype "power_in"))
      (node (ref "U3") (pin "P$12") (pinfunction "ROW13/K11_P$12") (pintype "bidirectional"))
    )
    (net (code "60") (name "/L5") (class "Default")
      (node (ref "D16") (pin "4") (pinfunction "L_4") (pintype "power_in"))
      (node (ref "D17") (pin "4") (pinfunction "L_4") (pintype "power_in"))
      (node (ref "D2") (pin "4") (pinfunction "L_4") (pintype "power_in"))
      (node (ref "D22") (pin "4") (pinfunction "L_4") (pintype "power_in"))
      (node (ref "D23") (pin "4") (pinfunction "L_4") (pintype "power_in"))
      (node (ref "D3") (pin "4") (pinfunction "L_4") (pintype "power_in"))
      (node (ref "D8") (pin "4") (pinfunction "L_4") (pintype "power_in"))
      (node (ref "D9") (pin "4") (pinfunction "L_4") (pintype "power_in"))
      (node (ref "U1") (pin "P$12") (pinfunction "ROW13/K11_P$12") (pintype "bidirectional"))
    )
    (net (code "61") (name "/M1") (class "Default")
      (node (ref "D10") (pin "3") (pinfunction "M_3") (pintype "power_in"))
      (node (ref "D11") (pin "3") (pinfunction "M_3") (pintype "power_in"))
      (node (ref "D12") (pin "3") (pinfunction "M_3") (pintype "power_in"))
      (node (ref "D13") (pin "3") (pinfunction "M_3") (pintype "power_in"))
      (node (ref "D4") (pin "3") (pinfunction "M_3") (pintype "power_in"))
      (node (ref "D5") (pin "3") (pinfunction "M_3") (pintype "power_in"))
      (node (ref "D6") (pin "3") (pinfunction "M_3") (pintype "power_in"))
      (node (ref "D7") (pin "3") (pinfunction "M_3") (pintype "power_in"))
      (node (ref "U2") (pin "P$13") (pinfunction "ROW12/K10_P$13") (pintype "bidirectional"))
    )
    (net (code "62") (name "/M3") (class "Default")
      (node (ref "D18") (pin "3") (pinfunction "M_3") (pintype "power_in"))
      (node (ref "D19") (pin "3") (pinfunction "M_3") (pintype "power_in"))
      (node (ref "D20") (pin "3") (pinfunction "M_3") (pintype "power_in"))
      (node (ref "D21") (pin "3") (pinfunction "M_3") (pintype "power_in"))
      (node (ref "D24") (pin "3") (pinfunction "M_3") (pintype "power_in"))
      (node (ref "D25") (pin "3") (pinfunction "M_3") (pintype "power_in"))
      (node (ref "D26") (pin "3") (pinfunction "M_3") (pintype "power_in"))
      (node (ref "D27") (pin "3") (pinfunction "M_3") (pintype "power_in"))
      (node (ref "U3") (pin "P$13") (pinfunction "ROW12/K10_P$13") (pintype "bidirectional"))
    )
    (net (code "63") (name "/M5") (class "Default")
      (node (ref "D16") (pin "3") (pinfunction "M_3") (pintype "power_in"))
      (node (ref "D17") (pin "3") (pinfunction "M_3") (pintype "power_in"))
      (node (ref "D2") (pin "3") (pinfunction "M_3") (pintype "power_in"))
      (node (ref "D22") (pin "3") (pinfunction "M_3") (pintype "power_in"))
      (node (ref "D23") (pin "3") (pinfunction "M_3") (pintype "power_in"))
      (node (ref "D3") (pin "3") (pinfunction "M_3") (pintype "power_in"))
      (node (ref "D8") (pin "3") (pinfunction "M_3") (pintype "power_in"))
      (node (ref "D9") (pin "3") (pinfunction "M_3") (pintype "power_in"))
      (node (ref "U1") (pin "P$13") (pinfunction "ROW12/K10_P$13") (pintype "bidirectional"))
    )
    (net (code "64") (name "/N1") (class "Default")
      (node (ref "D10") (pin "2") (pinfunction "N_2") (pintype "power_in"))
      (node (ref "D11") (pin "2") (pinfunction "N_2") (pintype "power_in"))
      (node (ref "D12") (pin "2") (pinfunction "N_2") (pintype "power_in"))
      (node (ref "D13") (pin "2") (pinfunction "N_2") (pintype "power_in"))
      (node (ref "D4") (pin "2") (pinfunction "N_2") (pintype "power_in"))
      (node (ref "D5") (pin "2") (pinfunction "N_2") (pintype "power_in"))
      (node (ref "D6") (pin "2") (pinfunction "N_2") (pintype "power_in"))
      (node (ref "D7") (pin "2") (pinfunction "N_2") (pintype "power_in"))
      (node (ref "U2") (pin "P$14") (pinfunction "ROW11/K9_P$14") (pintype "bidirectional"))
    )
    (net (code "65") (name "/N3") (class "Default")
      (node (ref "D18") (pin "2") (pinfunction "N_2") (pintype "power_in"))
      (node (ref "D19") (pin "2") (pinfunction "N_2") (pintype "power_in"))
      (node (ref "D20") (pin "2") (pinfunction "N_2") (pintype "power_in"))
      (node (ref "D21") (pin "2") (pinfunction "N_2") (pintype "power_in"))
      (node (ref "D24") (pin "2") (pinfunction "N_2") (pintype "power_in"))
      (node (ref "D25") (pin "2") (pinfunction "N_2") (pintype "power_in"))
      (node (ref "D26") (pin "2") (pinfunction "N_2") (pintype "power_in"))
      (node (ref "D27") (pin "2") (pinfunction "N_2") (pintype "power_in"))
      (node (ref "U3") (pin "P$14") (pinfunction "ROW11/K9_P$14") (pintype "bidirectional"))
    )
    (net (code "66") (name "/N5") (class "Default")
      (node (ref "D16") (pin "2") (pinfunction "N_2") (pintype "power_in"))
      (node (ref "D17") (pin "2") (pinfunction "N_2") (pintype "power_in"))
      (node (ref "D2") (pin "2") (pinfunction "N_2") (pintype "power_in"))
      (node (ref "D22") (pin "2") (pinfunction "N_2") (pintype "power_in"))
      (node (ref "D23") (pin "2") (pinfunction "N_2") (pintype "power_in"))
      (node (ref "D3") (pin "2") (pinfunction "N_2") (pintype "power_in"))
      (node (ref "D8") (pin "2") (pinfunction "N_2") (pintype "power_in"))
      (node (ref "D9") (pin "2") (pinfunction "N_2") (pintype "power_in"))
      (node (ref "U1") (pin "P$14") (pinfunction "ROW11/K9_P$14") (pintype "bidirectional"))
    )
    (net (code "67") (name "/P1") (class "Default")
      (node (ref "D10") (pin "1") (pinfunction "P_1") (pintype "power_in"))
      (node (ref "D11") (pin "1") (pinfunction "P_1") (pintype "power_in"))
      (node (ref "D12") (pin "1") (pinfunction "P_1") (pintype "power_in"))
      (node (ref "D13") (pin "1") (pinfunction "P_1") (pintype "power_in"))
      (node (ref "D4") (pin "1") (pinfunction "P_1") (pintype "power_in"))
      (node (ref "D5") (pin "1") (pinfunction "P_1") (pintype "power_in"))
      (node (ref "D6") (pin "1") (pinfunction "P_1") (pintype "power_in"))
      (node (ref "D7") (pin "1") (pinfunction "P_1") (pintype "power_in"))
      (node (ref "U2") (pin "P$19") (pinfunction "ROW6/K4_P$19") (pintype "bidirectional"))
    )
    (net (code "68") (name "/P3") (class "Default")
      (node (ref "D18") (pin "1") (pinfunction "P_1") (pintype "power_in"))
      (node (ref "D19") (pin "1") (pinfunction "P_1") (pintype "power_in"))
      (node (ref "D20") (pin "1") (pinfunction "P_1") (pintype "power_in"))
      (node (ref "D21") (pin "1") (pinfunction "P_1") (pintype "power_in"))
      (node (ref "D24") (pin "1") (pinfunction "P_1") (pintype "power_in"))
      (node (ref "D25") (pin "1") (pinfunction "P_1") (pintype "power_in"))
      (node (ref "D26") (pin "1") (pinfunction "P_1") (pintype "power_in"))
      (node (ref "D27") (pin "1") (pinfunction "P_1") (pintype "power_in"))
      (node (ref "U3") (pin "P$19") (pinfunction "ROW6/K4_P$19") (pintype "bidirectional"))
    )
    (net (code "69") (name "/P5") (class "Default")
      (node (ref "D16") (pin "1") (pinfunction "P_1") (pintype "power_in"))
      (node (ref "D17") (pin "1") (pinfunction "P_1") (pintype "power_in"))
      (node (ref "D2") (pin "1") (pinfunction "P_1") (pintype "power_in"))
      (node (ref "D22") (pin "1") (pinfunction "P_1") (pintype "power_in"))
      (node (ref "D23") (pin "1") (pinfunction "P_1") (pintype "power_in"))
      (node (ref "D3") (pin "1") (pinfunction "P_1") (pintype "power_in"))
      (node (ref "D8") (pin "1") (pinfunction "P_1") (pintype "power_in"))
      (node (ref "D9") (pin "1") (pinfunction "P_1") (pintype "power_in"))
      (node (ref "U1") (pin "P$19") (pinfunction "ROW6/K4_P$19") (pintype "bidirectional"))
    )
    (net (code "70") (name "5V+") (class "Default")
      (node (ref "C11") (pin "2") (pinfunction "2_2") (pintype "passive"))
      (node (ref "C12") (pin "2") (pinfunction "2_2") (pintype "passive"))
      (node (ref "C13") (pin "2") (pinfunction "2_2") (pintype "passive"))
      (node (ref "C14") (pin "2") (pinfunction "2_2") (pintype "passive"))
      (node (ref "C15") (pin "2") (pinfunction "2_2") (pintype "passive"))
      (node (ref "C16") (pin "2") (pinfunction "2_2") (pintype "passive"))
      (node (ref "U1") (pin "P$28") (pinfunction "VDD_P$28") (pintype "bidirectional"))
      (node (ref "U2") (pin "P$28") (pinfunction "VDD_P$28") (pintype "bidirectional"))
      (node (ref "U3") (pin "P$28") (pinfunction "VDD_P$28") (pintype "bidirectional"))
    )
    (net (code "71") (name "GND") (class "Default")
      (node (ref "C11") (pin "1") (pinfunction "1_1") (pintype "passive"))
      (node (ref "C12") (pin "1") (pinfunction "1_1") (pintype "passive"))
      (node (ref "C13") (pin "1") (pinfunction "1_1") (pintype "passive"))
      (node (ref "C14") (pin "1") (pinfunction "1_1") (pintype "passive"))
      (node (ref "C15") (pin "1") (pinfunction "1_1") (pintype "passive"))
      (node (ref "C16") (pin "1") (pinfunction "1_1") (pintype "passive"))
      (node (ref "U1") (pin "P$1") (pinfunction "VSS_P$1") (pintype "bidirectional"))
      (node (ref "U2") (pin "P$1") (pinfunction "VSS_P$1") (pintype "bidirectional"))
      (node (ref "U3") (pin "P$1") (pinfunction "VSS_P$1") (pintype "bidirectional"))
    )
    (net (code "72") (name "I2C_SCL") (class "Default")
      (node (ref "U1") (pin "P$27") (pinfunction "SDA_P$27") (pintype "bidirectional"))
      (node (ref "U2") (pin "P$27") (pinfunction "SDA_P$27") (pintype "bidirectional"))
      (node (ref "U3") (pin "P$27") (pinfunction "SDA_P$27") (pintype "bidirectional"))
    )
    (net (code "73") (name "I2C_SDA") (class "Default")
      (node (ref "U1") (pin "P$26") (pinfunction "SCL_P$26") (pintype "bidirectional"))
      (node (ref "U2") (pin "P$26") (pinfunction "SCL_P$26") (pintype "bidirectional"))
      (node (ref "U3") (pin "P$26") (pinfunction "SCL_P$26") (pintype "bidirectional"))
    )
    (net (code "74") (name "Net-(D14-Pad2)") (class "Default")
      (node (ref "D14") (pin "2") (pinfunction "2_2") (pintype "passive"))
      (node (ref "R14") (pin "2") (pinfunction "2_2") (pintype "passive"))
      (node (ref "R16") (pin "2") (pinfunction "2_2") (pintype "passive"))
      (node (ref "R18") (pin "2") (pinfunction "2_2") (pintype "passive"))
    )
    (net (code "75") (name "Net-(D15-Pad2)") (class "Default")
      (node (ref "D15") (pin "2") (pinfunction "2_2") (pintype "passive"))
      (node (ref "R15") (pin "2") (pinfunction "2_2") (pintype "passive"))
      (node (ref "R17") (pin "2") (pinfunction "2_2") (pintype "passive"))
      (node (ref "R19") (pin "2") (pinfunction "2_2") (pintype "passive"))
    )
    (net (code "76") (name "Net-(D28-Pad2)") (class "Default")
      (node (ref "D28") (pin "2") (pinfunction "2_2") (pintype "passive"))
      (node (ref "R20") (pin "2") (pinfunction "2_2") (pintype "passive"))
      (node (ref "R21") (pin "2") (pinfunction "2_2") (pintype "passive"))
      (node (ref "R22") (pin "2") (pinfunction "2_2") (pintype "passive"))
    )
    (net (code "77") (name "unconnected-(U1-ROW15{slash}K13{slash}INT-PadP$10)") (class "Default")
      (node (ref "U1") (pin "P$10") (pinfunction "ROW15/K13/INT_P$10") (pintype "bidirectional"))
    )
    (net (code "78") (name "unconnected-(U2-ROW15{slash}K13{slash}INT-PadP$10)") (class "Default")
      (node (ref "U2") (pin "P$10") (pinfunction "ROW15/K13/INT_P$10") (pintype "bidirectional"))
    )
    (net (code "79") (name "unconnected-(U3-ROW15{slash}K13{slash}INT-PadP$10)") (class "Default")
      (node (ref "U3") (pin "P$10") (pinfunction "ROW15/K13/INT_P$10") (pintype "bidirectional"))
    )
  )
)
